# SpectrumAnalyserRecruitProjCallum.net
KiCad netlist of a schematic drawn in Altium Designer
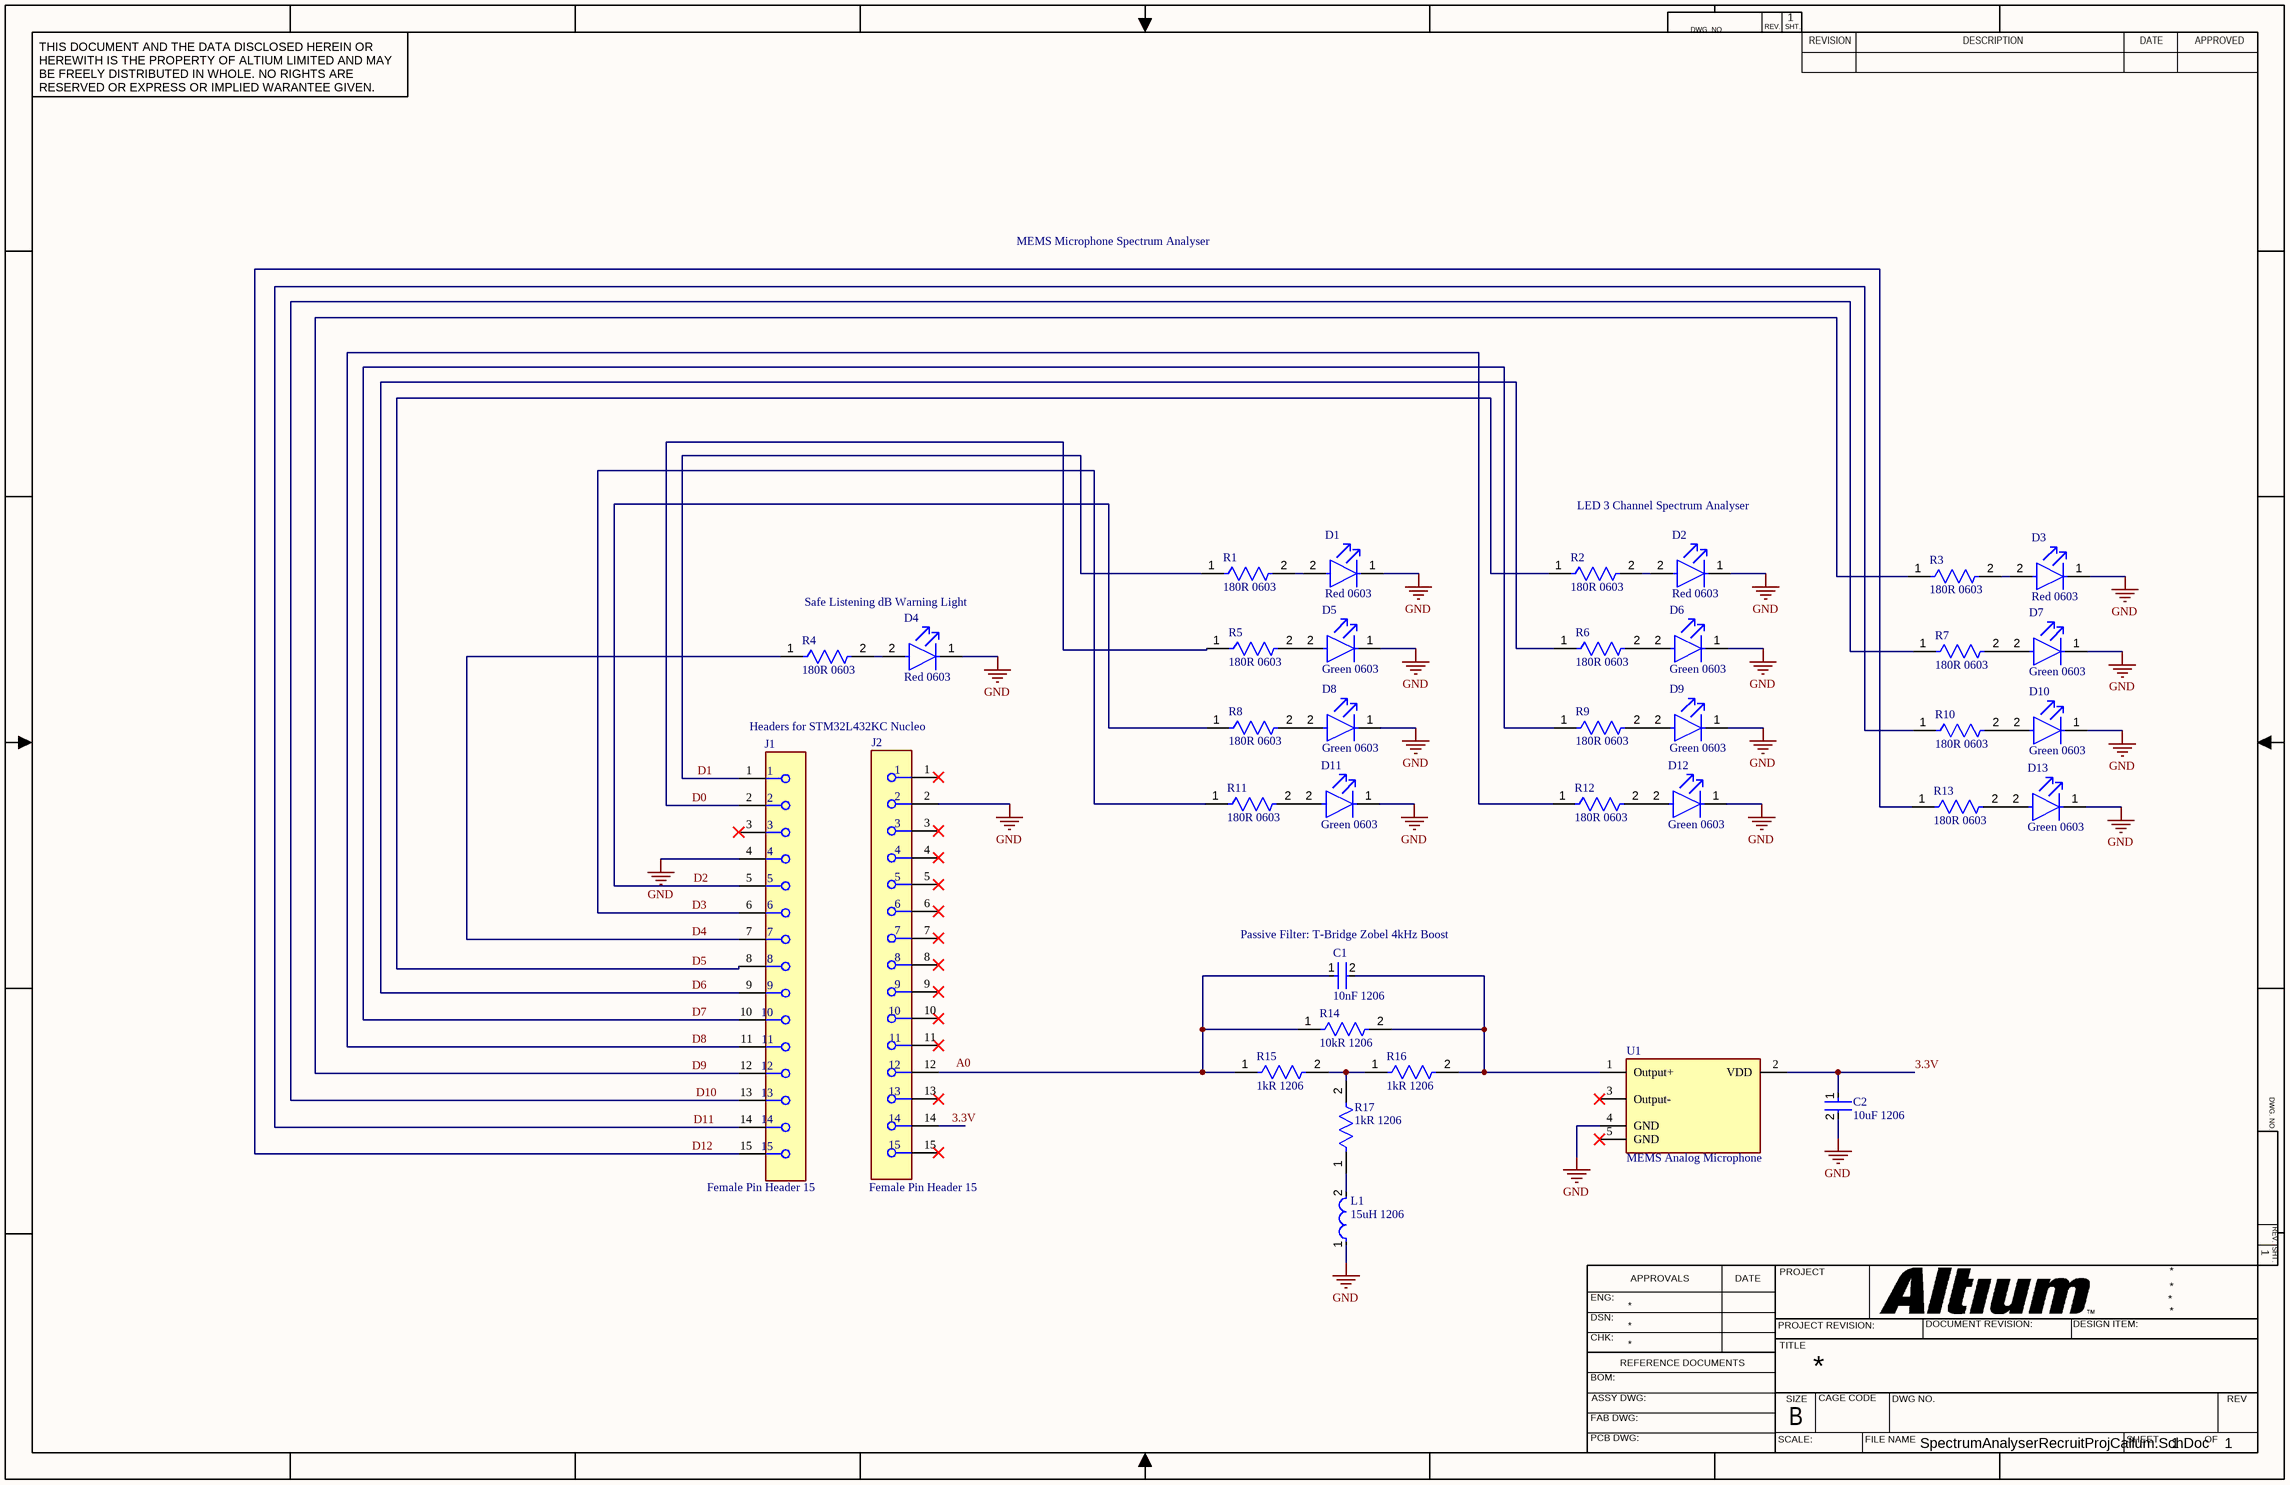
[diagram p0: SpectrumAnalyserRecruitProjCallum.SchDoc]

(export (version "E")
  (design (tool "Eeschema 10.0.6"))
  (components
    (comp (ref "C1")
      (value "10nF 1206")
      (footprint "FP-C1206C-EB-MFG")
      (description "C1206 10,000 pF C0G 5.00% 50 V")
      (fields
        (field (name "MANUFACTURER") "KEMET")
        (field (name "OCTOPART") "https://octopart.com/c1206c103j5gacauto-kemet-88376196")
      )
      (libsource (lib "Altium Content Vault") (part "b4654b650e69147ec39a6b967a45e02"))
    )
    (comp (ref "C2")
      (value "10uF 1206")
      (footprint "FP-C1206C-EH-MFG")
      (description "CAP CER 10UF 16V X7R 1206C1206C106K4RACAUTO")
      (fields
        (field (name "MANUFACTURER PART NUMBER") "C1206C106K4RACAUTO")
        (field (name "MANUFACTURER") "Kemet")
      )
      (libsource (lib "Altium Content Vault") (part "b4654b650e69147ec39a6b967a45e02"))
    )
    (comp (ref "D1")
      (value "Red 0603")
      (footprint "FP-SML-LX0603SIW-TR-MFG")
      (description "LED RED DIFFUSED SMD")
      (libsource (lib "Altium Content Vault") (part "8706943c75ba83719d021d2fdc84c58"))
    )
    (comp (ref "D2")
      (value "Red 0603")
      (footprint "FP-SML-LX0603SIW-TR-MFG")
      (description "LED RED DIFFUSED SMD")
      (libsource (lib "Altium Content Vault") (part "8706943c75ba83719d021d2fdc84c58"))
    )
    (comp (ref "D3")
      (value "Red 0603")
      (footprint "FP-SML-LX0603SIW-TR-MFG")
      (description "LED RED DIFFUSED SMD")
      (libsource (lib "Altium Content Vault") (part "8706943c75ba83719d021d2fdc84c58"))
    )
    (comp (ref "D4")
      (value "Red 0603")
      (footprint "FP-SML-LX0603SIW-TR-MFG")
      (description "LED RED DIFFUSED SMD")
      (libsource (lib "Altium Content Vault") (part "8706943c75ba83719d021d2fdc84c58"))
    )
    (comp (ref "D5")
      (value "Green 0603")
      (footprint "FP-LG_Q396-MFG")
      (description "LED GREEN DIFFUSED 0603 SMD")
      (libsource (lib "Altium Content Vault") (part "8706943c75ba83719d021d2fdc84c58"))
    )
    (comp (ref "D6")
      (value "Green 0603")
      (footprint "FP-LG_Q396-MFG")
      (description "LED GREEN DIFFUSED 0603 SMD")
      (libsource (lib "Altium Content Vault") (part "8706943c75ba83719d021d2fdc84c58"))
    )
    (comp (ref "D7")
      (value "Green 0603")
      (footprint "FP-LG_Q396-MFG")
      (description "LED GREEN DIFFUSED 0603 SMD")
      (libsource (lib "Altium Content Vault") (part "8706943c75ba83719d021d2fdc84c58"))
    )
    (comp (ref "D8")
      (value "Green 0603")
      (footprint "FP-LG_Q396-MFG")
      (description "LED GREEN DIFFUSED 0603 SMD")
      (libsource (lib "Altium Content Vault") (part "8706943c75ba83719d021d2fdc84c58"))
    )
    (comp (ref "D9")
      (value "Green 0603")
      (footprint "FP-LG_Q396-MFG")
      (description "LED GREEN DIFFUSED 0603 SMD")
      (libsource (lib "Altium Content Vault") (part "8706943c75ba83719d021d2fdc84c58"))
    )
    (comp (ref "D10")
      (value "Green 0603")
      (footprint "FP-LG_Q396-MFG")
      (description "LED GREEN DIFFUSED 0603 SMD")
      (libsource (lib "Altium Content Vault") (part "8706943c75ba83719d021d2fdc84c58"))
    )
    (comp (ref "D11")
      (value "Green 0603")
      (footprint "FP-LG_Q396-MFG")
      (description "LED GREEN DIFFUSED 0603 SMD")
      (libsource (lib "Altium Content Vault") (part "8706943c75ba83719d021d2fdc84c58"))
    )
    (comp (ref "D12")
      (value "Green 0603")
      (footprint "FP-LG_Q396-MFG")
      (description "LED GREEN DIFFUSED 0603 SMD")
      (libsource (lib "Altium Content Vault") (part "8706943c75ba83719d021d2fdc84c58"))
    )
    (comp (ref "D13")
      (value "Green 0603")
      (footprint "FP-LG_Q396-MFG")
      (description "LED GREEN DIFFUSED 0603 SMD")
      (libsource (lib "Altium Content Vault") (part "8706943c75ba83719d021d2fdc84c58"))
    )
    (comp (ref "J1")
      (value "Female Pin Header 15")
      (footprint "FP-SSW-115-01-T-S-MFG")
      (description "CONN RCPT 15POS 0.1 TIN PCB")
      (libsource (lib "") (part "de2cdd76613f87adcba81301aaab7e9_1"))
    )
    (comp (ref "J2")
      (value "Female Pin Header 15")
      (footprint "FP-SSW-115-01-T-S-MFG")
      (description "CONN RCPT 15POS 0.1 TIN PCB")
      (libsource (lib "Altium Content Vault") (part "de2cdd76613f87adcba81301aaab7e9"))
    )
    (comp (ref "L1")
      (value "15uH 1206")
      (footprint "FP-LQH31CN_03-MFG")
      (description "Wire Wound Ferrite Inductor for General Circuits 15μH ±5% 3.9Ω 90mA 1206")
      (fields (field (name "TOLERANCE") "5%"))
      (libsource (lib "Altium Content Vault") (part "725321dda6339637d4d059423bc1c3c"))
    )
    (comp (ref "R1")
      (value "180R 0603")
      (footprint "FP-AF0603-MFG")
      (description "Anti-Sulfurated Chip Resistors Automotive Grade 180Ω 1% 100ppm/°C 0603")
      (fields (field (name "TOLERANCE") "1%"))
      (libsource (lib "Altium Content Vault") (part "1029c3af85768c4190bb7ad29bc67b5"))
    )
    (comp (ref "R2")
      (value "180R 0603")
      (footprint "FP-AF0603-MFG")
      (description "Anti-Sulfurated Chip Resistors Automotive Grade 180Ω 1% 100ppm/°C 0603")
      (fields (field (name "TOLERANCE") "1%"))
      (libsource (lib "Altium Content Vault") (part "1029c3af85768c4190bb7ad29bc67b5"))
    )
    (comp (ref "R3")
      (value "180R 0603")
      (footprint "FP-AF0603-MFG")
      (description "Anti-Sulfurated Chip Resistors Automotive Grade 180Ω 1% 100ppm/°C 0603")
      (fields (field (name "TOLERANCE") "1%"))
      (libsource (lib "Altium Content Vault") (part "1029c3af85768c4190bb7ad29bc67b5"))
    )
    (comp (ref "R4")
      (value "180R 0603")
      (footprint "FP-AF0603-MFG")
      (description "Anti-Sulfurated Chip Resistors Automotive Grade 180Ω 1% 100ppm/°C 0603")
      (fields (field (name "TOLERANCE") "1%"))
      (libsource (lib "Altium Content Vault") (part "1029c3af85768c4190bb7ad29bc67b5"))
    )
    (comp (ref "R5")
      (value "180R 0603")
      (footprint "FP-AF0603-MFG")
      (description "Anti-Sulfurated Chip Resistors Automotive Grade 180Ω 1% 100ppm/°C 0603")
      (fields (field (name "TOLERANCE") "1%"))
      (libsource (lib "Altium Content Vault") (part "1029c3af85768c4190bb7ad29bc67b5"))
    )
    (comp (ref "R6")
      (value "180R 0603")
      (footprint "FP-AF0603-MFG")
      (description "Anti-Sulfurated Chip Resistors Automotive Grade 180Ω 1% 100ppm/°C 0603")
      (fields (field (name "TOLERANCE") "1%"))
      (libsource (lib "Altium Content Vault") (part "1029c3af85768c4190bb7ad29bc67b5"))
    )
    (comp (ref "R7")
      (value "180R 0603")
      (footprint "FP-AF0603-MFG")
      (description "Anti-Sulfurated Chip Resistors Automotive Grade 180Ω 1% 100ppm/°C 0603")
      (fields (field (name "TOLERANCE") "1%"))
      (libsource (lib "Altium Content Vault") (part "1029c3af85768c4190bb7ad29bc67b5"))
    )
    (comp (ref "R8")
      (value "180R 0603")
      (footprint "FP-AF0603-MFG")
      (description "Anti-Sulfurated Chip Resistors Automotive Grade 180Ω 1% 100ppm/°C 0603")
      (fields (field (name "TOLERANCE") "1%"))
      (libsource (lib "Altium Content Vault") (part "1029c3af85768c4190bb7ad29bc67b5"))
    )
    (comp (ref "R9")
      (value "180R 0603")
      (footprint "FP-AF0603-MFG")
      (description "Anti-Sulfurated Chip Resistors Automotive Grade 180Ω 1% 100ppm/°C 0603")
      (fields (field (name "TOLERANCE") "1%"))
      (libsource (lib "Altium Content Vault") (part "1029c3af85768c4190bb7ad29bc67b5"))
    )
    (comp (ref "R10")
      (value "180R 0603")
      (footprint "FP-AF0603-MFG")
      (description "Anti-Sulfurated Chip Resistors Automotive Grade 180Ω 1% 100ppm/°C 0603")
      (fields (field (name "TOLERANCE") "1%"))
      (libsource (lib "Altium Content Vault") (part "1029c3af85768c4190bb7ad29bc67b5"))
    )
    (comp (ref "R11")
      (value "180R 0603")
      (footprint "FP-AF0603-MFG")
      (description "Anti-Sulfurated Chip Resistors Automotive Grade 180Ω 1% 100ppm/°C 0603")
      (fields (field (name "TOLERANCE") "1%"))
      (libsource (lib "Altium Content Vault") (part "1029c3af85768c4190bb7ad29bc67b5"))
    )
    (comp (ref "R12")
      (value "180R 0603")
      (footprint "FP-AF0603-MFG")
      (description "Anti-Sulfurated Chip Resistors Automotive Grade 180Ω 1% 100ppm/°C 0603")
      (fields (field (name "TOLERANCE") "1%"))
      (libsource (lib "Altium Content Vault") (part "1029c3af85768c4190bb7ad29bc67b5"))
    )
    (comp (ref "R13")
      (value "180R 0603")
      (footprint "FP-AF0603-MFG")
      (description "Anti-Sulfurated Chip Resistors Automotive Grade 180Ω 1% 100ppm/°C 0603")
      (fields (field (name "TOLERANCE") "1%"))
      (libsource (lib "Altium Content Vault") (part "1029c3af85768c4190bb7ad29bc67b5"))
    )
    (comp (ref "R14")
      (value "10kR 1206")
      (footprint "FP-RMCF1206-MFG")
      (description "10kΩ ±1% 0.25W 1206 Thick Film Chip Resistor AEC-Q200 compliant")
      (fields (field (name "TOLERANCE") "1%"))
      (libsource (lib "Altium Content Vault") (part "1029c3af85768c4190bb7ad29bc67b5"))
    )
    (comp (ref "R15")
      (value "1kR 1206")
      (footprint "FP-RMCF1206-IPC_A")
      (description "1kΩ ±5% 0.25W 1206 Thick Film Chip Resistor AEC-Q200 compliant")
      (fields (field (name "TOLERANCE") "5%"))
      (libsource (lib "Altium Content Vault") (part "1029c3af85768c4190bb7ad29bc67b5"))
    )
    (comp (ref "R16")
      (value "1kR 1206")
      (footprint "FP-RMCF1206-IPC_A")
      (description "1kΩ ±5% 0.25W 1206 Thick Film Chip Resistor AEC-Q200 compliant")
      (fields (field (name "TOLERANCE") "5%"))
      (libsource (lib "Altium Content Vault") (part "1029c3af85768c4190bb7ad29bc67b5"))
    )
    (comp (ref "R17")
      (value "1kR 1206")
      (footprint "FP-RMCF1206-IPC_A")
      (description "1kΩ ±5% 0.25W 1206 Thick Film Chip Resistor AEC-Q200 compliant")
      (fields (field (name "TOLERANCE") "5%"))
      (libsource (lib "Altium Content Vault") (part "1029c3af85768c4190bb7ad29bc67b5"))
    )
    (comp (ref "U1")
      (value "MEMS Analog Microphone")
      (footprint "FP-PG-LLGA-5-MFG")
      (description "MICROPHONES_DIFFERENTIAT PG-LLGA IM73A135V01XTSA1")
      (libsource (lib "Altium Content Vault") (part "bda7ab8b8ded3209b46862693234890"))
    )
  )
  (nets
    (net (code "1") (name "/3.3V") (class "Default")
      (node (ref "C2") (pin "1") (pinfunction "1_1") (pintype "passive"))
      (node (ref "J2") (pin "14") (pinfunction "14_14") (pintype "passive"))
      (node (ref "U1") (pin "2") (pinfunction "VDD_2") (pintype "power_in"))
    )
    (net (code "3") (name "/D0") (class "Default")
      (node (ref "J1") (pin "2") (pinfunction "2_2") (pintype "passive"))
      (node (ref "R5") (pin "1") (pinfunction "1_1") (pintype "passive"))
    )
    (net (code "4") (name "/D1") (class "Default")
      (node (ref "J1") (pin "1") (pinfunction "1_1") (pintype "passive"))
      (node (ref "R1") (pin "1") (pinfunction "1_1") (pintype "passive"))
    )
    (net (code "5") (name "/D2") (class "Default")
      (node (ref "J1") (pin "5") (pinfunction "5_5") (pintype "passive"))
      (node (ref "R8") (pin "1") (pinfunction "1_1") (pintype "passive"))
    )
    (net (code "6") (name "/D3") (class "Default")
      (node (ref "J1") (pin "6") (pinfunction "6_6") (pintype "passive"))
      (node (ref "R11") (pin "1") (pinfunction "1_1") (pintype "passive"))
    )
    (net (code "7") (name "/D4") (class "Default")
      (node (ref "J1") (pin "7") (pinfunction "7_7") (pintype "passive"))
      (node (ref "R4") (pin "1") (pinfunction "1_1") (pintype "passive"))
    )
    (net (code "8") (name "/D5") (class "Default")
      (node (ref "J1") (pin "8") (pinfunction "8_8") (pintype "passive"))
      (node (ref "R2") (pin "1") (pinfunction "1_1") (pintype "passive"))
    )
    (net (code "9") (name "/D6") (class "Default")
      (node (ref "J1") (pin "9") (pinfunction "9_9") (pintype "passive"))
      (node (ref "R6") (pin "1") (pinfunction "1_1") (pintype "passive"))
    )
    (net (code "10") (name "/D7") (class "Default")
      (node (ref "J1") (pin "10") (pinfunction "10_10") (pintype "passive"))
      (node (ref "R9") (pin "1") (pinfunction "1_1") (pintype "passive"))
    )
    (net (code "11") (name "/D8") (class "Default")
      (node (ref "J1") (pin "11") (pinfunction "11_11") (pintype "passive"))
      (node (ref "R12") (pin "1") (pinfunction "1_1") (pintype "passive"))
    )
    (net (code "12") (name "/D9") (class "Default")
      (node (ref "J1") (pin "12") (pinfunction "12_12") (pintype "passive"))
      (node (ref "R3") (pin "1") (pinfunction "1_1") (pintype "passive"))
    )
    (net (code "13") (name "/D10") (class "Default")
      (node (ref "J1") (pin "13") (pinfunction "13_13") (pintype "passive"))
      (node (ref "R7") (pin "1") (pinfunction "1_1") (pintype "passive"))
    )
    (net (code "14") (name "/D11") (class "Default")
      (node (ref "J1") (pin "14") (pinfunction "14_14") (pintype "passive"))
      (node (ref "R10") (pin "1") (pinfunction "1_1") (pintype "passive"))
    )
    (net (code "15") (name "/D12") (class "Default")
      (node (ref "J1") (pin "15") (pinfunction "15_15") (pintype "passive"))
      (node (ref "R13") (pin "1") (pinfunction "1_1") (pintype "passive"))
    )
    (net (code "16") (name "GND") (class "Default")
      (node (ref "C2") (pin "2") (pinfunction "2_2") (pintype "passive"))
      (node (ref "D1") (pin "1") (pinfunction "C_1") (pintype "passive"))
      (node (ref "D10") (pin "1") (pinfunction "C_1") (pintype "passive"))
      (node (ref "D11") (pin "1") (pinfunction "C_1") (pintype "passive"))
      (node (ref "D12") (pin "1") (pinfunction "C_1") (pintype "passive"))
      (node (ref "D13") (pin "1") (pinfunction "C_1") (pintype "passive"))
      (node (ref "D2") (pin "1") (pinfunction "C_1") (pintype "passive"))
      (node (ref "D3") (pin "1") (pinfunction "C_1") (pintype "passive"))
      (node (ref "D4") (pin "1") (pinfunction "C_1") (pintype "passive"))
      (node (ref "D5") (pin "1") (pinfunction "C_1") (pintype "passive"))
      (node (ref "D6") (pin "1") (pinfunction "C_1") (pintype "passive"))
      (node (ref "D7") (pin "1") (pinfunction "C_1") (pintype "passive"))
      (node (ref "D8") (pin "1") (pinfunction "C_1") (pintype "passive"))
      (node (ref "D9") (pin "1") (pinfunction "C_1") (pintype "passive"))
      (node (ref "J1") (pin "4") (pinfunction "4_4") (pintype "passive"))
      (node (ref "J2") (pin "2") (pinfunction "2_2") (pintype "passive"))
      (node (ref "L1") (pin "1") (pinfunction "1_1") (pintype "passive"))
      (node (ref "U1") (pin "4") (pinfunction "GND_4") (pintype "power_in"))
    )
    (net (code "17") (name "Net-(C1-Pad1)") (class "Default")
      (node (ref "C1") (pin "1") (pinfunction "1_1") (pintype "passive"))
      (node (ref "J2") (pin "12") (pinfunction "12_12") (pintype "passive"))
      (node (ref "R14") (pin "1") (pinfunction "1_1") (pintype "passive"))
      (node (ref "R15") (pin "1") (pinfunction "1_1") (pintype "passive"))
    )
    (net (code "18") (name "Net-(D1-A)") (class "Default")
      (node (ref "D1") (pin "2") (pinfunction "A_2") (pintype "passive"))
      (node (ref "R1") (pin "2") (pinfunction "2_2") (pintype "passive"))
    )
    (net (code "19") (name "Net-(D2-A)") (class "Default")
      (node (ref "D2") (pin "2") (pinfunction "A_2") (pintype "passive"))
      (node (ref "R2") (pin "2") (pinfunction "2_2") (pintype "passive"))
    )
    (net (code "20") (name "Net-(D3-A)") (class "Default")
      (node (ref "D3") (pin "2") (pinfunction "A_2") (pintype "passive"))
      (node (ref "R3") (pin "2") (pinfunction "2_2") (pintype "passive"))
    )
    (net (code "21") (name "Net-(D4-A)") (class "Default")
      (node (ref "D4") (pin "2") (pinfunction "A_2") (pintype "passive"))
      (node (ref "R4") (pin "2") (pinfunction "2_2") (pintype "passive"))
    )
    (net (code "22") (name "Net-(D5-A)") (class "Default")
      (node (ref "D5") (pin "2") (pinfunction "A_2") (pintype "passive"))
      (node (ref "R5") (pin "2") (pinfunction "2_2") (pintype "passive"))
    )
    (net (code "23") (name "Net-(D6-A)") (class "Default")
      (node (ref "D6") (pin "2") (pinfunction "A_2") (pintype "passive"))
      (node (ref "R6") (pin "2") (pinfunction "2_2") (pintype "passive"))
    )
    (net (code "24") (name "Net-(D7-A)") (class "Default")
      (node (ref "D7") (pin "2") (pinfunction "A_2") (pintype "passive"))
      (node (ref "R7") (pin "2") (pinfunction "2_2") (pintype "passive"))
    )
    (net (code "25") (name "Net-(D8-A)") (class "Default")
      (node (ref "D8") (pin "2") (pinfunction "A_2") (pintype "passive"))
      (node (ref "R8") (pin "2") (pinfunction "2_2") (pintype "passive"))
    )
    (net (code "26") (name "Net-(D9-A)") (class "Default")
      (node (ref "D9") (pin "2") (pinfunction "A_2") (pintype "passive"))
      (node (ref "R9") (pin "2") (pinfunction "2_2") (pintype "passive"))
    )
    (net (code "27") (name "Net-(D10-A)") (class "Default")
      (node (ref "D10") (pin "2") (pinfunction "A_2") (pintype "passive"))
      (node (ref "R10") (pin "2") (pinfunction "2_2") (pintype "passive"))
    )
    (net (code "28") (name "Net-(D11-A)") (class "Default")
      (node (ref "D11") (pin "2") (pinfunction "A_2") (pintype "passive"))
      (node (ref "R11") (pin "2") (pinfunction "2_2") (pintype "passive"))
    )
    (net (code "29") (name "Net-(D12-A)") (class "Default")
      (node (ref "D12") (pin "2") (pinfunction "A_2") (pintype "passive"))
      (node (ref "R12") (pin "2") (pinfunction "2_2") (pintype "passive"))
    )
    (net (code "30") (name "Net-(D13-A)") (class "Default")
      (node (ref "D13") (pin "2") (pinfunction "A_2") (pintype "passive"))
      (node (ref "R13") (pin "2") (pinfunction "2_2") (pintype "passive"))
    )
    (net (code "31") (name "Net-(L1-Pad2)") (class "Default")
      (node (ref "L1") (pin "2") (pinfunction "2_2") (pintype "passive"))
      (node (ref "R17") (pin "1") (pinfunction "1_1") (pintype "passive"))
    )
    (net (code "32") (name "Net-(R15-Pad2)") (class "Default")
      (node (ref "R15") (pin "2") (pinfunction "2_2") (pintype "passive"))
      (node (ref "R16") (pin "1") (pinfunction "1_1") (pintype "passive"))
      (node (ref "R17") (pin "2") (pinfunction "2_2") (pintype "passive"))
    )
    (net (code "33") (name "Net-(U1-Output+)") (class "Default")
      (node (ref "C1") (pin "2") (pinfunction "2_2") (pintype "passive"))
      (node (ref "R14") (pin "2") (pinfunction "2_2") (pintype "passive"))
      (node (ref "R16") (pin "2") (pinfunction "2_2") (pintype "passive"))
      (node (ref "U1") (pin "1") (pinfunction "Output+_1") (pintype "passive"))
    )
    (net (code "34") (name "unconnected-(J1-Pad3)") (class "Default")
      (node (ref "J1") (pin "3") (pinfunction "3_3") (pintype "passive+no_connect"))
    )
    (net (code "35") (name "unconnected-(J2-Pad1)") (class "Default")
      (node (ref "J2") (pin "1") (pinfunction "1_1") (pintype "passive+no_connect"))
    )
    (net (code "36") (name "unconnected-(J2-Pad3)") (class "Default")
      (node (ref "J2") (pin "3") (pinfunction "3_3") (pintype "passive+no_connect"))
    )
    (net (code "37") (name "unconnected-(J2-Pad4)") (class "Default")
      (node (ref "J2") (pin "4") (pinfunction "4_4") (pintype "passive+no_connect"))
    )
    (net (code "38") (name "unconnected-(J2-Pad5)") (class "Default")
      (node (ref "J2") (pin "5") (pinfunction "5_5") (pintype "passive+no_connect"))
    )
    (net (code "39") (name "unconnected-(J2-Pad6)") (class "Default")
      (node (ref "J2") (pin "6") (pinfunction "6_6") (pintype "passive+no_connect"))
    )
    (net (code "40") (name "unconnected-(J2-Pad7)") (class "Default")
      (node (ref "J2") (pin "7") (pinfunction "7_7") (pintype "passive+no_connect"))
    )
    (net (code "41") (name "unconnected-(J2-Pad8)") (class "Default")
      (node (ref "J2") (pin "8") (pinfunction "8_8") (pintype "passive+no_connect"))
    )
    (net (code "42") (name "unconnected-(J2-Pad9)") (class "Default")
      (node (ref "J2") (pin "9") (pinfunction "9_9") (pintype "passive+no_connect"))
    )
    (net (code "43") (name "unconnected-(J2-Pad10)") (class "Default")
      (node (ref "J2") (pin "10") (pinfunction "10_10") (pintype "passive+no_connect"))
    )
    (net (code "44") (name "unconnected-(J2-Pad11)") (class "Default")
      (node (ref "J2") (pin "11") (pinfunction "11_11") (pintype "passive+no_connect"))
    )
    (net (code "45") (name "unconnected-(J2-Pad13)") (class "Default")
      (node (ref "J2") (pin "13") (pinfunction "13_13") (pintype "passive+no_connect"))
    )
    (net (code "46") (name "unconnected-(J2-Pad15)") (class "Default")
      (node (ref "J2") (pin "15") (pinfunction "15_15") (pintype "passive+no_connect"))
    )
    (net (code "47") (name "unconnected-(U1-GND-Pad5)") (class "Default")
      (node (ref "U1") (pin "5") (pinfunction "GND_5") (pintype "power_in+no_connect"))
    )
    (net (code "48") (name "unconnected-(U1-Output--Pad3)") (class "Default")
      (node (ref "U1") (pin "3") (pinfunction "Output-_3") (pintype "passive+no_connect"))
    )
  )
)
